# GainCHR.net
KiCad netlist of a schematic drawn in Altium Designer
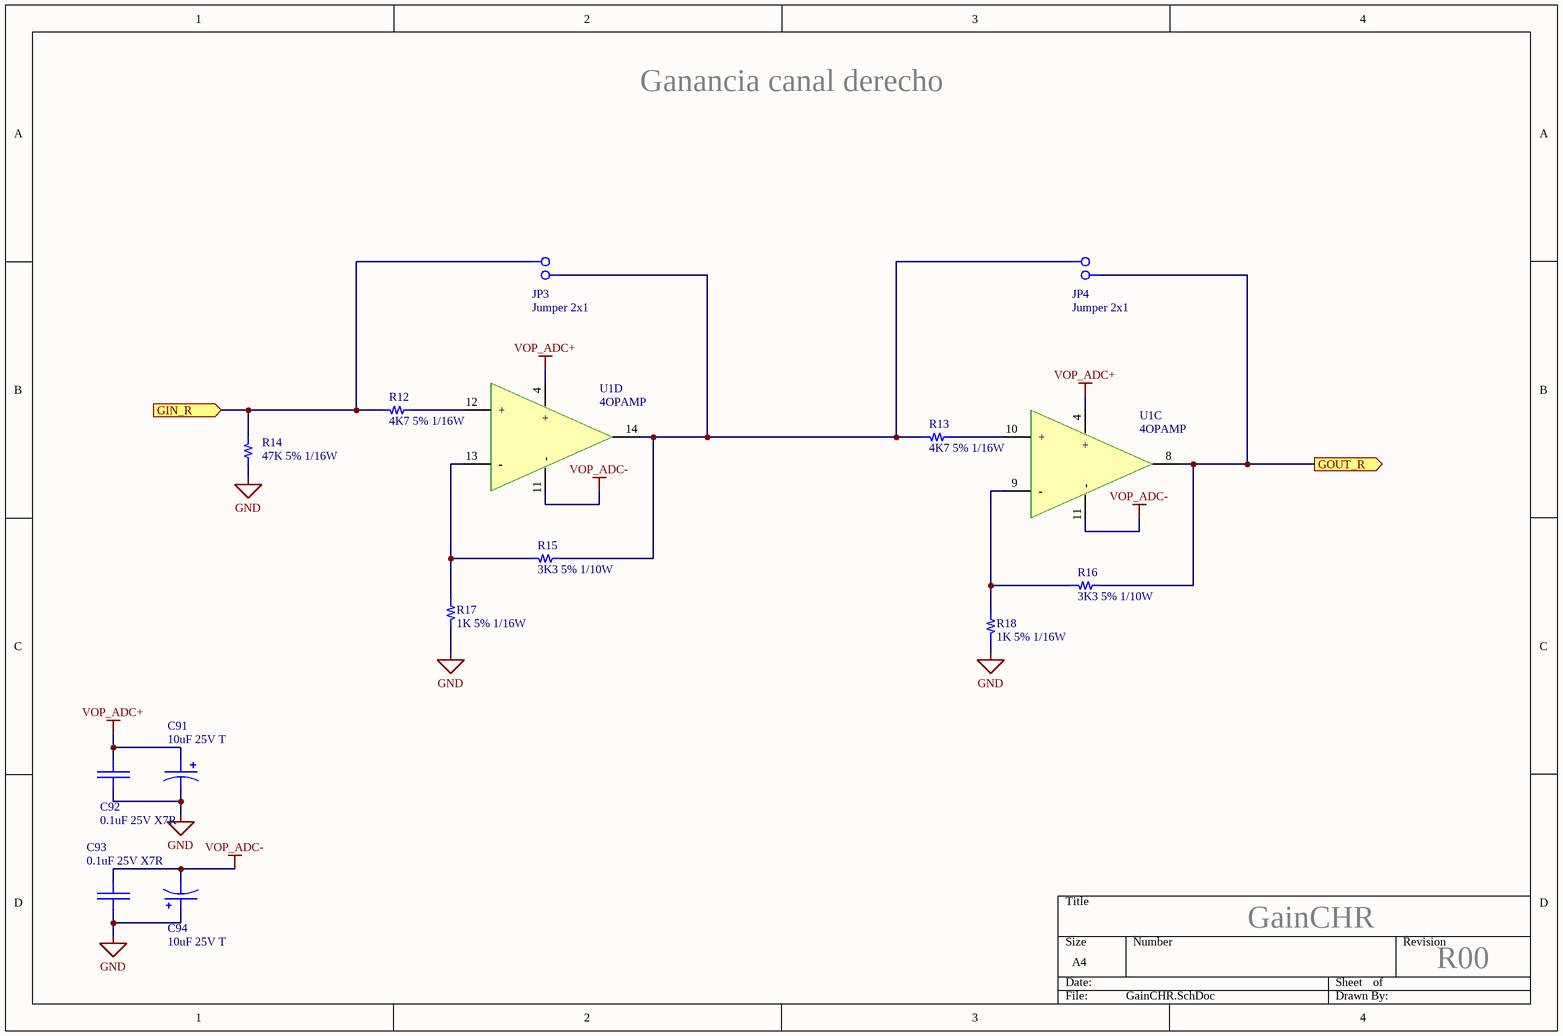
[diagram p0: GainCHR.SchDoc]

(export (version "E")
  (design (tool "Eeschema 10.0.6"))
  (components
    (comp (ref "C91")
      (value "10uF 25V T")
      (footprint "TANT")
      (description "Capacitor polarizado")
      (libsource (lib "Radios_Comunitarias") (part "CapaPol"))
    )
    (comp (ref "C92")
      (value "0.1uF 25V X7R")
      (footprint "C_0805")
      (description "Capacitor de placas paralelas")
      (libsource (lib "Radios_Comunitarias") (part "Capacitor"))
    )
    (comp (ref "C93")
      (value "0.1uF 25V X7R")
      (footprint "C_0805")
      (description "Capacitor de placas paralelas")
      (libsource (lib "Radios_Comunitarias") (part "Capacitor"))
    )
    (comp (ref "C94")
      (value "10uF 25V T")
      (footprint "TANT")
      (description "Capacitor polarizado")
      (libsource (lib "Radios_Comunitarias") (part "CapaPol"))
    )
    (comp (ref "JP3")
      (value "Jumper 2x1")
      (footprint "Conn_2_1")
      (libsource (lib "Radios_Comunitarias") (part "Jumper 2x1"))
    )
    (comp (ref "JP4")
      (value "Jumper 2x1")
      (footprint "Conn_2_1")
      (libsource (lib "Radios_Comunitarias") (part "Jumper 2x1"))
    )
    (comp (ref "R12")
      (value "4K7 5% 1/16W")
      (footprint "R_0805")
      (description "Resistencia")
      (libsource (lib "Radios_Comunitarias") (part "Resistor"))
    )
    (comp (ref "R13")
      (value "4K7 5% 1/16W")
      (footprint "R_0805")
      (description "Resistencia")
      (libsource (lib "Radios_Comunitarias") (part "Resistor"))
    )
    (comp (ref "R14")
      (value "47K 5% 1/16W")
      (footprint "R_0805")
      (description "Resistencia")
      (libsource (lib "Radios_Comunitarias") (part "Resistor"))
    )
    (comp (ref "R15")
      (value "3K3 5% 1/10W")
      (footprint "R_0805")
      (description "Resistencia")
      (libsource (lib "Radios_Comunitarias") (part "Resistor"))
    )
    (comp (ref "R16")
      (value "3K3 5% 1/10W")
      (footprint "R_0805")
      (description "Resistencia")
      (libsource (lib "Radios_Comunitarias") (part "Resistor"))
    )
    (comp (ref "R17")
      (value "1K 5% 1/16W")
      (footprint "R_0805")
      (description "Resistencia")
      (libsource (lib "Radios_Comunitarias") (part "Resistor"))
    )
    (comp (ref "R18")
      (value "1K 5% 1/16W")
      (footprint "R_0805")
      (description "Resistencia")
      (libsource (lib "Radios_Comunitarias") (part "Resistor"))
    )
    (comp (ref "U1")
      (value "4OPAMP")
      (footprint "SOIC14")
      (description "Integrado con 4 operacionales")
      (libsource (lib "Radios_Comunitarias") (part "4OPAMP"))
    )
  )
  (nets
    (net (code "1") (name "/GIN_R") (class "Default")
      (node (ref "JP3") (pin "1") (pinfunction "1_1") (pintype "passive"))
      (node (ref "R12") (pin "2") (pinfunction "2_2") (pintype "passive"))
      (node (ref "R14") (pin "2") (pinfunction "2_2") (pintype "passive"))
    )
    (net (code "2") (name "/GOUT_R") (class "Default")
      (node (ref "JP4") (pin "2") (pinfunction "2_2") (pintype "passive"))
      (node (ref "R16") (pin "1") (pinfunction "1_1") (pintype "passive"))
      (node (ref "U1") (pin "8") (pinfunction "OUT_8") (pintype "passive"))
    )
    (net (code "3") (name "GND") (class "Default")
      (node (ref "C91") (pin "2") (pinfunction "2_2") (pintype "passive"))
      (node (ref "C92") (pin "2") (pinfunction "2_2") (pintype "passive"))
      (node (ref "C93") (pin "2") (pinfunction "2_2") (pintype "passive"))
      (node (ref "C94") (pin "1") (pinfunction "1_1") (pintype "passive"))
      (node (ref "R14") (pin "1") (pinfunction "1_1") (pintype "passive"))
      (node (ref "R17") (pin "2") (pinfunction "2_2") (pintype "passive"))
      (node (ref "R18") (pin "2") (pinfunction "2_2") (pintype "passive"))
    )
    (net (code "4") (name "Net-(R12-Pad1)") (class "Default")
      (node (ref "R12") (pin "1") (pinfunction "1_1") (pintype "passive"))
      (node (ref "U1") (pin "12") (pinfunction "+_12") (pintype "passive"))
    )
    (net (code "5") (name "Net-(R13-Pad1)") (class "Default")
      (node (ref "R13") (pin "1") (pinfunction "1_1") (pintype "passive"))
      (node (ref "U1") (pin "10") (pinfunction "+_10") (pintype "passive"))
    )
    (net (code "6") (name "Net-(R15-Pad2)") (class "Default")
      (node (ref "R15") (pin "2") (pinfunction "2_2") (pintype "passive"))
      (node (ref "R17") (pin "1") (pinfunction "1_1") (pintype "passive"))
      (node (ref "U1") (pin "13") (pinfunction "-_13") (pintype "passive"))
    )
    (net (code "7") (name "Net-(R16-Pad2)") (class "Default")
      (node (ref "R16") (pin "2") (pinfunction "2_2") (pintype "passive"))
      (node (ref "R18") (pin "1") (pinfunction "1_1") (pintype "passive"))
      (node (ref "U1") (pin "9") (pinfunction "-_9") (pintype "passive"))
    )
    (net (code "8") (name "Net-(U1D-OUT)") (class "Default")
      (node (ref "JP3") (pin "2") (pinfunction "2_2") (pintype "passive"))
      (node (ref "JP4") (pin "1") (pinfunction "1_1") (pintype "passive"))
      (node (ref "R13") (pin "2") (pinfunction "2_2") (pintype "passive"))
      (node (ref "R15") (pin "1") (pinfunction "1_1") (pintype "passive"))
      (node (ref "U1") (pin "14") (pinfunction "OUT_14") (pintype "passive"))
    )
    (net (code "9") (name "VOP_ADC+") (class "Default")
      (node (ref "C91") (pin "1") (pinfunction "1_1") (pintype "passive"))
      (node (ref "C92") (pin "1") (pinfunction "1_1") (pintype "passive"))
      (node (ref "U1") (pin "4") (pinfunction "+_4") (pintype "power_in"))
    )
    (net (code "10") (name "VOP_ADC-") (class "Default")
      (node (ref "C93") (pin "1") (pinfunction "1_1") (pintype "passive"))
      (node (ref "C94") (pin "2") (pinfunction "2_2") (pintype "passive"))
      (node (ref "U1") (pin "11") (pinfunction "-_11") (pintype "passive"))
    )
  )
)
